# INA260_SFS.net
KiCad netlist of a schematic drawn in EAGLE
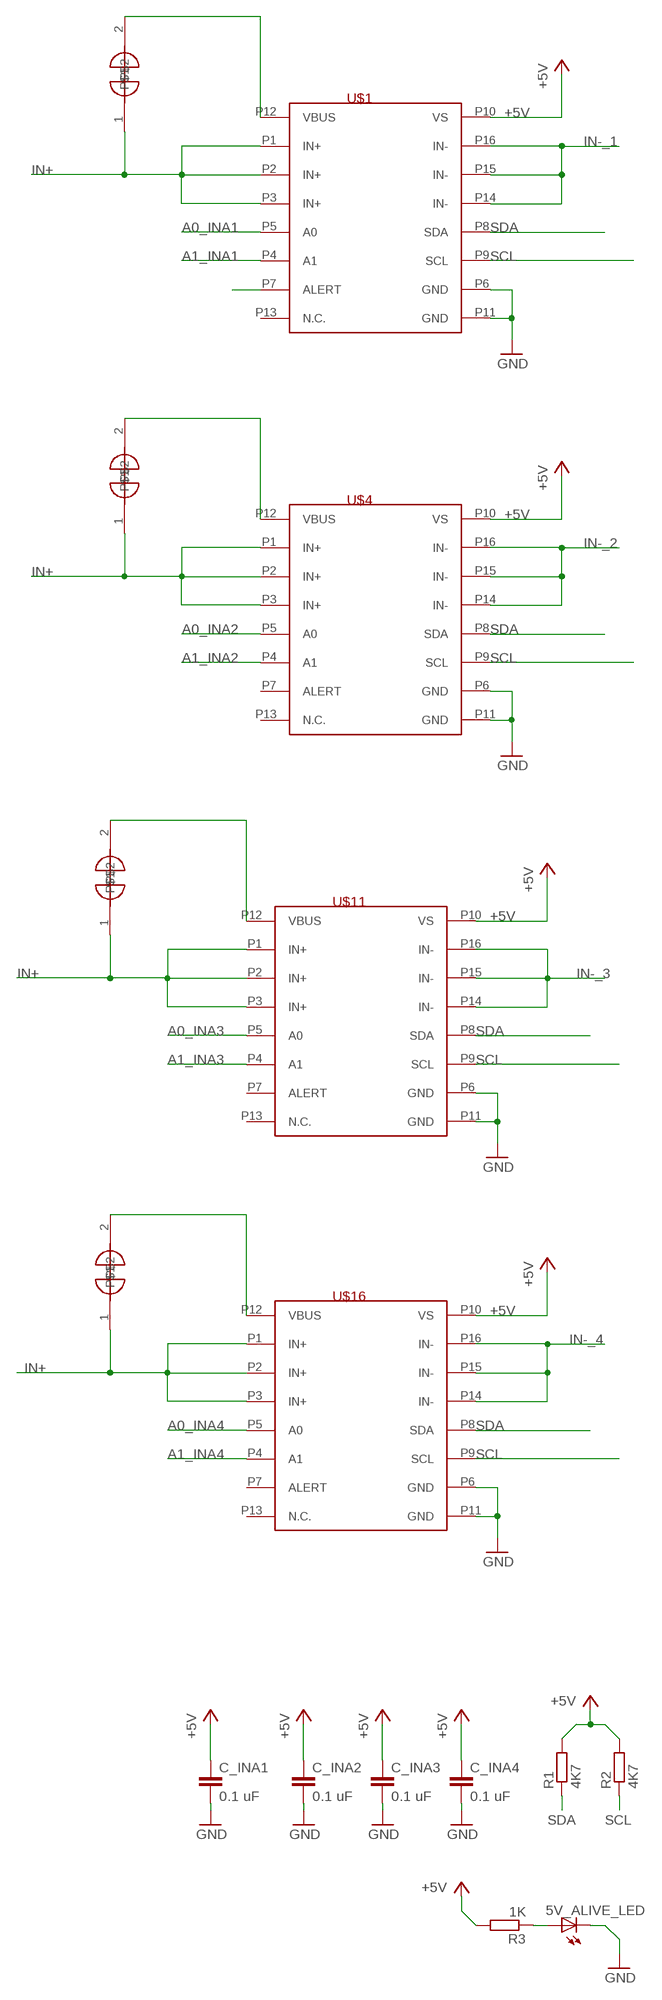
[diagram p0: schematic, sheet 1]
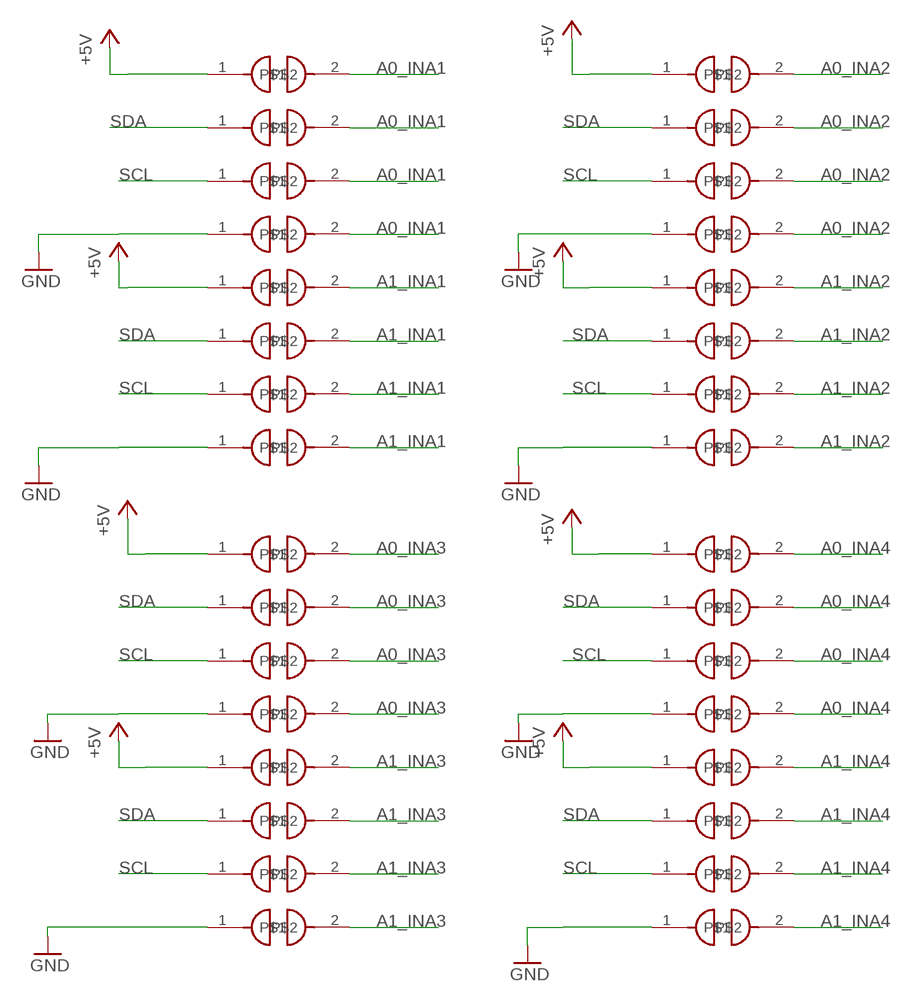
[diagram p1: schematic, sheet 2]
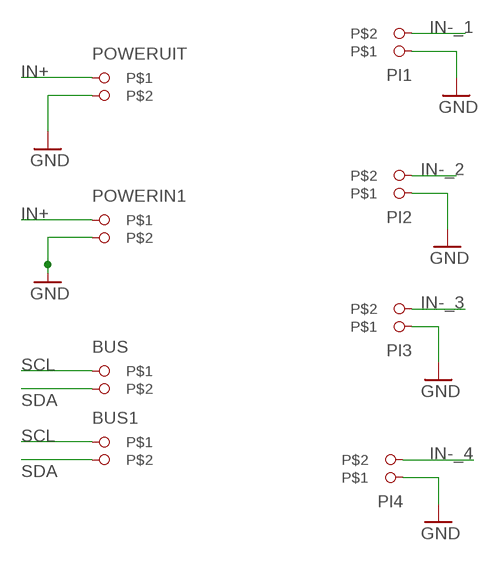
[diagram p2: schematic, sheet 3]
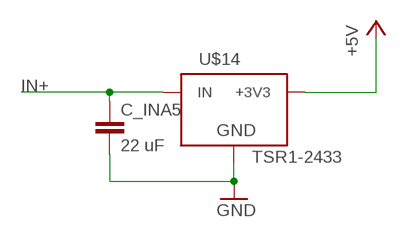
[diagram p3: schematic, sheet 4]

(export (version "E")
  (design (tool "Eeschema 10.0.6"))
  (components
    (comp (ref "BUS")
      (value "CON_3.81MM2_SIDE")
      (footprint "eagle-import:CON_3.81MM2")
      (libsource (lib "eagle-import") (part "CON_3.81MM2_SIDE"))
    )
    (comp (ref "BUS1")
      (value "CON_3.81MM2_SIDE")
      (footprint "eagle-import:CON_3.81MM2")
      (libsource (lib "eagle-import") (part "CON_3.81MM2_SIDE"))
    )
    (comp (ref "PI1")
      (value "CON_3.81MM2_SIDE")
      (footprint "eagle-import:CON_3.81MM2")
      (libsource (lib "eagle-import") (part "CON_3.81MM2_SIDE"))
    )
    (comp (ref "PI2")
      (value "CON_3.81MM2_SIDE")
      (footprint "eagle-import:CON_3.81MM2")
      (libsource (lib "eagle-import") (part "CON_3.81MM2_SIDE"))
    )
    (comp (ref "PI3")
      (value "CON_3.81MM2_SIDE")
      (footprint "eagle-import:CON_3.81MM2")
      (libsource (lib "eagle-import") (part "CON_3.81MM2_SIDE"))
    )
    (comp (ref "PI4")
      (value "CON_3.81MM2_SIDE")
      (footprint "eagle-import:CON_3.81MM2")
      (libsource (lib "eagle-import") (part "CON_3.81MM2_SIDE"))
    )
    (comp (ref "POWERIN1")
      (value "CON_3.81MM2_SIDE")
      (footprint "eagle-import:CON_3.81MM2")
      (libsource (lib "eagle-import") (part "CON_3.81MM2_SIDE"))
    )
    (comp (ref "POWERUIT")
      (value "CON_3.81MM2_SIDE")
      (footprint "eagle-import:CON_3.81MM2")
      (libsource (lib "eagle-import") (part "CON_3.81MM2_SIDE"))
    )
    (comp (ref "U$38")
      (value "JUMPER")
      (footprint "eagle-import:SOLDERJUMPER_ARROW_NOPASTE")
      (libsource (lib "eagle-import") (part "JUMPER"))
    )
    (comp (ref "U$39")
      (value "JUMPER")
      (footprint "eagle-import:SOLDERJUMPER_ARROW_NOPASTE")
      (libsource (lib "eagle-import") (part "JUMPER"))
    )
    (comp (ref "U$40")
      (value "JUMPER")
      (footprint "eagle-import:SOLDERJUMPER_ARROW_NOPASTE")
      (libsource (lib "eagle-import") (part "JUMPER"))
    )
    (comp (ref "U$41")
      (value "JUMPER")
      (footprint "eagle-import:SOLDERJUMPER_ARROW_NOPASTE")
      (libsource (lib "eagle-import") (part "JUMPER"))
    )
    (comp (ref "U$42")
      (value "JUMPER")
      (footprint "eagle-import:SOLDERJUMPER_ARROW_NOPASTE")
      (libsource (lib "eagle-import") (part "JUMPER"))
    )
    (comp (ref "U$43")
      (value "JUMPER")
      (footprint "eagle-import:SOLDERJUMPER_ARROW_NOPASTE")
      (libsource (lib "eagle-import") (part "JUMPER"))
    )
    (comp (ref "U$44")
      (value "JUMPER")
      (footprint "eagle-import:SOLDERJUMPER_ARROW_NOPASTE")
      (libsource (lib "eagle-import") (part "JUMPER"))
    )
    (comp (ref "U$45")
      (value "JUMPER")
      (footprint "eagle-import:SOLDERJUMPER_ARROW_NOPASTE")
      (libsource (lib "eagle-import") (part "JUMPER"))
    )
    (comp (ref "U$46")
      (value "JUMPER")
      (footprint "eagle-import:SOLDERJUMPER_ARROW_NOPASTE")
      (libsource (lib "eagle-import") (part "JUMPER"))
    )
    (comp (ref "U$47")
      (value "JUMPER")
      (footprint "eagle-import:SOLDERJUMPER_ARROW_NOPASTE")
      (libsource (lib "eagle-import") (part "JUMPER"))
    )
    (comp (ref "U$48")
      (value "JUMPER")
      (footprint "eagle-import:SOLDERJUMPER_ARROW_NOPASTE")
      (libsource (lib "eagle-import") (part "JUMPER"))
    )
    (comp (ref "U$49")
      (value "JUMPER")
      (footprint "eagle-import:SOLDERJUMPER_ARROW_NOPASTE")
      (libsource (lib "eagle-import") (part "JUMPER"))
    )
    (comp (ref "U$50")
      (value "JUMPER")
      (footprint "eagle-import:SOLDERJUMPER_ARROW_NOPASTE")
      (libsource (lib "eagle-import") (part "JUMPER"))
    )
    (comp (ref "U$51")
      (value "JUMPER")
      (footprint "eagle-import:SOLDERJUMPER_ARROW_NOPASTE")
      (libsource (lib "eagle-import") (part "JUMPER"))
    )
    (comp (ref "U$52")
      (value "JUMPER")
      (footprint "eagle-import:SOLDERJUMPER_ARROW_NOPASTE")
      (libsource (lib "eagle-import") (part "JUMPER"))
    )
    (comp (ref "U$53")
      (value "JUMPER")
      (footprint "eagle-import:SOLDERJUMPER_ARROW_NOPASTE")
      (libsource (lib "eagle-import") (part "JUMPER"))
    )
    (comp (ref "U$54")
      (value "JUMPER")
      (footprint "eagle-import:SOLDERJUMPER_ARROW_NOPASTE")
      (libsource (lib "eagle-import") (part "JUMPER"))
    )
    (comp (ref "U$55")
      (value "JUMPER")
      (footprint "eagle-import:SOLDERJUMPER_ARROW_NOPASTE")
      (libsource (lib "eagle-import") (part "JUMPER"))
    )
    (comp (ref "U$56")
      (value "JUMPER")
      (footprint "eagle-import:SOLDERJUMPER_ARROW_NOPASTE")
      (libsource (lib "eagle-import") (part "JUMPER"))
    )
    (comp (ref "U$57")
      (value "JUMPER")
      (footprint "eagle-import:SOLDERJUMPER_ARROW_NOPASTE")
      (libsource (lib "eagle-import") (part "JUMPER"))
    )
    (comp (ref "U$58")
      (value "JUMPER")
      (footprint "eagle-import:SOLDERJUMPER_ARROW_NOPASTE")
      (libsource (lib "eagle-import") (part "JUMPER"))
    )
    (comp (ref "U$59")
      (value "JUMPER")
      (footprint "eagle-import:SOLDERJUMPER_ARROW_NOPASTE")
      (libsource (lib "eagle-import") (part "JUMPER"))
    )
    (comp (ref "U$60")
      (value "JUMPER")
      (footprint "eagle-import:SOLDERJUMPER_ARROW_NOPASTE")
      (libsource (lib "eagle-import") (part "JUMPER"))
    )
    (comp (ref "U$61")
      (value "JUMPER")
      (footprint "eagle-import:SOLDERJUMPER_ARROW_NOPASTE")
      (libsource (lib "eagle-import") (part "JUMPER"))
    )
    (comp (ref "U$62")
      (value "JUMPER")
      (footprint "eagle-import:SOLDERJUMPER_ARROW_NOPASTE")
      (libsource (lib "eagle-import") (part "JUMPER"))
    )
    (comp (ref "U$63")
      (value "JUMPER")
      (footprint "eagle-import:SOLDERJUMPER_ARROW_NOPASTE")
      (libsource (lib "eagle-import") (part "JUMPER"))
    )
    (comp (ref "U$64")
      (value "JUMPER")
      (footprint "eagle-import:SOLDERJUMPER_ARROW_NOPASTE")
      (libsource (lib "eagle-import") (part "JUMPER"))
    )
    (comp (ref "U$65")
      (value "JUMPER")
      (footprint "eagle-import:SOLDERJUMPER_ARROW_NOPASTE")
      (libsource (lib "eagle-import") (part "JUMPER"))
    )
    (comp (ref "U$66")
      (value "JUMPER")
      (footprint "eagle-import:SOLDERJUMPER_ARROW_NOPASTE")
      (libsource (lib "eagle-import") (part "JUMPER"))
    )
    (comp (ref "U$67")
      (value "JUMPER")
      (footprint "eagle-import:SOLDERJUMPER_ARROW_NOPASTE")
      (libsource (lib "eagle-import") (part "JUMPER"))
    )
    (comp (ref "U$68")
      (value "JUMPER")
      (footprint "eagle-import:SOLDERJUMPER_ARROW_NOPASTE")
      (libsource (lib "eagle-import") (part "JUMPER"))
    )
    (comp (ref "U$69")
      (value "JUMPER")
      (footprint "eagle-import:SOLDERJUMPER_ARROW_NOPASTE")
      (libsource (lib "eagle-import") (part "JUMPER"))
    )
    (comp (ref "5V_ALIVE_LED")
      (value "LEDSMT1206")
      (footprint "eagle-import:1206")
      (libsource (lib "eagle-import") (part "LEDSMT1206"))
    )
    (comp (ref "C_INA1")
      (value "0.1 uF")
      (footprint "eagle-import:RESC0805_N")
      (libsource (lib "eagle-import") (part "CAPACITOR_0805_N"))
    )
    (comp (ref "C_INA2")
      (value "0.1 uF")
      (footprint "eagle-import:RESC0805_N")
      (libsource (lib "eagle-import") (part "CAPACITOR_0805_N"))
    )
    (comp (ref "C_INA3")
      (value "0.1 uF")
      (footprint "eagle-import:RESC0805_N")
      (libsource (lib "eagle-import") (part "CAPACITOR_0805_N"))
    )
    (comp (ref "C_INA4")
      (value "0.1 uF")
      (footprint "eagle-import:RESC0805_N")
      (libsource (lib "eagle-import") (part "CAPACITOR_0805_N"))
    )
    (comp (ref "R1")
      (value "4K7")
      (footprint "eagle-import:M0805")
      (libsource (lib "eagle-import") (part "R-EU_M0805"))
    )
    (comp (ref "R2")
      (value "4K7")
      (footprint "eagle-import:M0805")
      (libsource (lib "eagle-import") (part "R-EU_M0805"))
    )
    (comp (ref "R3")
      (value "1K")
      (footprint "eagle-import:M0805")
      (libsource (lib "eagle-import") (part "R-EU_M0805"))
    )
    (comp (ref "U$1")
      (value "INA260")
      (footprint "eagle-import:TSSOP16L")
      (libsource (lib "eagle-import") (part "INA260"))
    )
    (comp (ref "U$4")
      (value "INA260")
      (footprint "eagle-import:TSSOP16L")
      (libsource (lib "eagle-import") (part "INA260"))
    )
    (comp (ref "U$5")
      (value "CLOSEDJUMPER")
      (footprint "eagle-import:SOLDERJUMPER_CLOSEDWIRE")
      (libsource (lib "eagle-import") (part "CLOSEDJUMPER"))
    )
    (comp (ref "U$6")
      (value "CLOSEDJUMPER")
      (footprint "eagle-import:SOLDERJUMPER_CLOSEDWIRE")
      (libsource (lib "eagle-import") (part "CLOSEDJUMPER"))
    )
    (comp (ref "U$11")
      (value "INA260")
      (footprint "eagle-import:TSSOP16L")
      (libsource (lib "eagle-import") (part "INA260"))
    )
    (comp (ref "U$12")
      (value "CLOSEDJUMPER")
      (footprint "eagle-import:SOLDERJUMPER_CLOSEDWIRE")
      (libsource (lib "eagle-import") (part "CLOSEDJUMPER"))
    )
    (comp (ref "U$16")
      (value "INA260")
      (footprint "eagle-import:TSSOP16L")
      (libsource (lib "eagle-import") (part "INA260"))
    )
    (comp (ref "U$17")
      (value "CLOSEDJUMPER")
      (footprint "eagle-import:SOLDERJUMPER_CLOSEDWIRE")
      (libsource (lib "eagle-import") (part "CLOSEDJUMPER"))
    )
    (comp (ref "C_INA5")
      (value "22 uF")
      (footprint "eagle-import:RESC0805_N")
      (libsource (lib "eagle-import") (part "CAPACITOR_0805_N"))
    )
    (comp (ref "U$14")
      (value "TSR1-2433")
      (footprint "eagle-import:TSR-1")
      (libsource (lib "eagle-import") (part "TSR1-2433"))
    )
  )
  (nets
    (net (code "1") (name "+5V") (class "Default")
      (node (ref "C_INA1") (pin "1") (pinfunction "1_1") (pintype "passive"))
      (node (ref "C_INA2") (pin "1") (pinfunction "1_1") (pintype "passive"))
      (node (ref "C_INA3") (pin "1") (pinfunction "1_1") (pintype "passive"))
      (node (ref "C_INA4") (pin "1") (pinfunction "1_1") (pintype "passive"))
      (node (ref "R1") (pin "2") (pinfunction "2_2") (pintype "passive"))
      (node (ref "R2") (pin "2") (pinfunction "2_2") (pintype "passive"))
      (node (ref "R3") (pin "2") (pinfunction "2_2") (pintype "passive"))
      (node (ref "U$1") (pin "P10") (pinfunction "VS_P10") (pintype "bidirectional"))
      (node (ref "U$11") (pin "P10") (pinfunction "VS_P10") (pintype "bidirectional"))
      (node (ref "U$14") (pin "3") (pinfunction "+3V3_3") (pintype "power_in"))
      (node (ref "U$16") (pin "P10") (pinfunction "VS_P10") (pintype "bidirectional"))
      (node (ref "U$4") (pin "P10") (pinfunction "VS_P10") (pintype "bidirectional"))
      (node (ref "U$41") (pin "1") (pinfunction "P$1_1") (pintype "bidirectional"))
      (node (ref "U$45") (pin "1") (pinfunction "P$1_1") (pintype "bidirectional"))
      (node (ref "U$49") (pin "1") (pinfunction "P$1_1") (pintype "bidirectional"))
      (node (ref "U$53") (pin "1") (pinfunction "P$1_1") (pintype "bidirectional"))
      (node (ref "U$57") (pin "1") (pinfunction "P$1_1") (pintype "bidirectional"))
      (node (ref "U$61") (pin "1") (pinfunction "P$1_1") (pintype "bidirectional"))
      (node (ref "U$65") (pin "1") (pinfunction "P$1_1") (pintype "bidirectional"))
      (node (ref "U$69") (pin "1") (pinfunction "P$1_1") (pintype "bidirectional"))
    )
    (net (code "2") (name "A0_INA1") (class "Default")
      (node (ref "U$1") (pin "P5") (pinfunction "A0_P5") (pintype "bidirectional"))
      (node (ref "U$42") (pin "2") (pinfunction "P$2_2") (pintype "bidirectional"))
      (node (ref "U$43") (pin "2") (pinfunction "P$2_2") (pintype "bidirectional"))
      (node (ref "U$44") (pin "2") (pinfunction "P$2_2") (pintype "bidirectional"))
      (node (ref "U$45") (pin "2") (pinfunction "P$2_2") (pintype "bidirectional"))
    )
    (net (code "3") (name "A0_INA2") (class "Default")
      (node (ref "U$4") (pin "P5") (pinfunction "A0_P5") (pintype "bidirectional"))
      (node (ref "U$50") (pin "2") (pinfunction "P$2_2") (pintype "bidirectional"))
      (node (ref "U$51") (pin "2") (pinfunction "P$2_2") (pintype "bidirectional"))
      (node (ref "U$52") (pin "2") (pinfunction "P$2_2") (pintype "bidirectional"))
      (node (ref "U$53") (pin "2") (pinfunction "P$2_2") (pintype "bidirectional"))
    )
    (net (code "4") (name "A0_INA3") (class "Default")
      (node (ref "U$11") (pin "P5") (pinfunction "A0_P5") (pintype "bidirectional"))
      (node (ref "U$58") (pin "2") (pinfunction "P$2_2") (pintype "bidirectional"))
      (node (ref "U$59") (pin "2") (pinfunction "P$2_2") (pintype "bidirectional"))
      (node (ref "U$60") (pin "2") (pinfunction "P$2_2") (pintype "bidirectional"))
      (node (ref "U$61") (pin "2") (pinfunction "P$2_2") (pintype "bidirectional"))
    )
    (net (code "5") (name "A0_INA4") (class "Default")
      (node (ref "U$16") (pin "P5") (pinfunction "A0_P5") (pintype "bidirectional"))
      (node (ref "U$66") (pin "2") (pinfunction "P$2_2") (pintype "bidirectional"))
      (node (ref "U$67") (pin "2") (pinfunction "P$2_2") (pintype "bidirectional"))
      (node (ref "U$68") (pin "2") (pinfunction "P$2_2") (pintype "bidirectional"))
      (node (ref "U$69") (pin "2") (pinfunction "P$2_2") (pintype "bidirectional"))
    )
    (net (code "6") (name "A1_INA1") (class "Default")
      (node (ref "U$1") (pin "P4") (pinfunction "A1_P4") (pintype "bidirectional"))
      (node (ref "U$38") (pin "2") (pinfunction "P$2_2") (pintype "bidirectional"))
      (node (ref "U$39") (pin "2") (pinfunction "P$2_2") (pintype "bidirectional"))
      (node (ref "U$40") (pin "2") (pinfunction "P$2_2") (pintype "bidirectional"))
      (node (ref "U$41") (pin "2") (pinfunction "P$2_2") (pintype "bidirectional"))
    )
    (net (code "7") (name "A1_INA2") (class "Default")
      (node (ref "U$4") (pin "P4") (pinfunction "A1_P4") (pintype "bidirectional"))
      (node (ref "U$46") (pin "2") (pinfunction "P$2_2") (pintype "bidirectional"))
      (node (ref "U$47") (pin "2") (pinfunction "P$2_2") (pintype "bidirectional"))
      (node (ref "U$48") (pin "2") (pinfunction "P$2_2") (pintype "bidirectional"))
      (node (ref "U$49") (pin "2") (pinfunction "P$2_2") (pintype "bidirectional"))
    )
    (net (code "8") (name "A1_INA3") (class "Default")
      (node (ref "U$11") (pin "P4") (pinfunction "A1_P4") (pintype "bidirectional"))
      (node (ref "U$54") (pin "2") (pinfunction "P$2_2") (pintype "bidirectional"))
      (node (ref "U$55") (pin "2") (pinfunction "P$2_2") (pintype "bidirectional"))
      (node (ref "U$56") (pin "2") (pinfunction "P$2_2") (pintype "bidirectional"))
      (node (ref "U$57") (pin "2") (pinfunction "P$2_2") (pintype "bidirectional"))
    )
    (net (code "9") (name "A1_INA4") (class "Default")
      (node (ref "U$16") (pin "P4") (pinfunction "A1_P4") (pintype "bidirectional"))
      (node (ref "U$62") (pin "2") (pinfunction "P$2_2") (pintype "bidirectional"))
      (node (ref "U$63") (pin "2") (pinfunction "P$2_2") (pintype "bidirectional"))
      (node (ref "U$64") (pin "2") (pinfunction "P$2_2") (pintype "bidirectional"))
      (node (ref "U$65") (pin "2") (pinfunction "P$2_2") (pintype "bidirectional"))
    )
    (net (code "10") (name "GND") (class "Default")
      (node (ref "5V_ALIVE_LED") (pin "C") (pinfunction "C_C") (pintype "passive"))
      (node (ref "C_INA1") (pin "2") (pinfunction "2_2") (pintype "passive"))
      (node (ref "C_INA2") (pin "2") (pinfunction "2_2") (pintype "passive"))
      (node (ref "C_INA3") (pin "2") (pinfunction "2_2") (pintype "passive"))
      (node (ref "C_INA4") (pin "2") (pinfunction "2_2") (pintype "passive"))
      (node (ref "C_INA5") (pin "2") (pinfunction "2_2") (pintype "passive"))
      (node (ref "PI1") (pin "P$1") (pinfunction "P$1_P$1") (pintype "bidirectional"))
      (node (ref "PI2") (pin "P$1") (pinfunction "P$1_P$1") (pintype "bidirectional"))
      (node (ref "PI3") (pin "P$1") (pinfunction "P$1_P$1") (pintype "bidirectional"))
      (node (ref "PI4") (pin "P$1") (pinfunction "P$1_P$1") (pintype "bidirectional"))
      (node (ref "POWERIN1") (pin "P$2") (pinfunction "P$2_P$2") (pintype "bidirectional"))
      (node (ref "POWERUIT") (pin "P$2") (pinfunction "P$2_P$2") (pintype "bidirectional"))
      (node (ref "U$1") (pin "P11") (pinfunction "GND_P11") (pintype "bidirectional"))
      (node (ref "U$1") (pin "P6") (pinfunction "GND_P6") (pintype "bidirectional"))
      (node (ref "U$11") (pin "P11") (pinfunction "GND_P11") (pintype "bidirectional"))
      (node (ref "U$11") (pin "P6") (pinfunction "GND_P6") (pintype "bidirectional"))
      (node (ref "U$14") (pin "2") (pinfunction "GND_2") (pintype "power_in"))
      (node (ref "U$16") (pin "P11") (pinfunction "GND_P11") (pintype "bidirectional"))
      (node (ref "U$16") (pin "P6") (pinfunction "GND_P6") (pintype "bidirectional"))
      (node (ref "U$38") (pin "1") (pinfunction "P$1_1") (pintype "bidirectional"))
      (node (ref "U$4") (pin "P11") (pinfunction "GND_P11") (pintype "bidirectional"))
      (node (ref "U$4") (pin "P6") (pinfunction "GND_P6") (pintype "bidirectional"))
      (node (ref "U$42") (pin "1") (pinfunction "P$1_1") (pintype "bidirectional"))
      (node (ref "U$46") (pin "1") (pinfunction "P$1_1") (pintype "bidirectional"))
      (node (ref "U$50") (pin "1") (pinfunction "P$1_1") (pintype "bidirectional"))
      (node (ref "U$54") (pin "1") (pinfunction "P$1_1") (pintype "bidirectional"))
      (node (ref "U$58") (pin "1") (pinfunction "P$1_1") (pintype "bidirectional"))
      (node (ref "U$62") (pin "1") (pinfunction "P$1_1") (pintype "bidirectional"))
      (node (ref "U$66") (pin "1") (pinfunction "P$1_1") (pintype "bidirectional"))
    )
    (net (code "11") (name "IN+") (class "Default")
      (node (ref "C_INA5") (pin "1") (pinfunction "1_1") (pintype "passive"))
      (node (ref "POWERIN1") (pin "P$1") (pinfunction "P$1_P$1") (pintype "bidirectional"))
      (node (ref "POWERUIT") (pin "P$1") (pinfunction "P$1_P$1") (pintype "bidirectional"))
      (node (ref "U$1") (pin "P1") (pinfunction "IN+_P1") (pintype "bidirectional"))
      (node (ref "U$1") (pin "P2") (pinfunction "IN+_P2") (pintype "bidirectional"))
      (node (ref "U$1") (pin "P3") (pinfunction "IN+_P3") (pintype "bidirectional"))
      (node (ref "U$11") (pin "P1") (pinfunction "IN+_P1") (pintype "bidirectional"))
      (node (ref "U$11") (pin "P2") (pinfunction "IN+_P2") (pintype "bidirectional"))
      (node (ref "U$11") (pin "P3") (pinfunction "IN+_P3") (pintype "bidirectional"))
      (node (ref "U$12") (pin "1") (pinfunction "P$1_1") (pintype "bidirectional"))
      (node (ref "U$14") (pin "1") (pinfunction "IN_1") (pintype "power_in"))
      (node (ref "U$16") (pin "P1") (pinfunction "IN+_P1") (pintype "bidirectional"))
      (node (ref "U$16") (pin "P2") (pinfunction "IN+_P2") (pintype "bidirectional"))
      (node (ref "U$16") (pin "P3") (pinfunction "IN+_P3") (pintype "bidirectional"))
      (node (ref "U$17") (pin "1") (pinfunction "P$1_1") (pintype "bidirectional"))
      (node (ref "U$4") (pin "P1") (pinfunction "IN+_P1") (pintype "bidirectional"))
      (node (ref "U$4") (pin "P2") (pinfunction "IN+_P2") (pintype "bidirectional"))
      (node (ref "U$4") (pin "P3") (pinfunction "IN+_P3") (pintype "bidirectional"))
      (node (ref "U$5") (pin "1") (pinfunction "P$1_1") (pintype "bidirectional"))
      (node (ref "U$6") (pin "1") (pinfunction "P$1_1") (pintype "bidirectional"))
    )
    (net (code "12") (name "IN-_1") (class "Default")
      (node (ref "PI1") (pin "P$2") (pinfunction "P$2_P$2") (pintype "bidirectional"))
      (node (ref "U$1") (pin "P14") (pinfunction "IN-_P14") (pintype "bidirectional"))
      (node (ref "U$1") (pin "P15") (pinfunction "IN-_P15") (pintype "bidirectional"))
      (node (ref "U$1") (pin "P16") (pinfunction "IN-_P16") (pintype "bidirectional"))
    )
    (net (code "13") (name "IN-_2") (class "Default")
      (node (ref "PI2") (pin "P$2") (pinfunction "P$2_P$2") (pintype "bidirectional"))
      (node (ref "U$4") (pin "P14") (pinfunction "IN-_P14") (pintype "bidirectional"))
      (node (ref "U$4") (pin "P15") (pinfunction "IN-_P15") (pintype "bidirectional"))
      (node (ref "U$4") (pin "P16") (pinfunction "IN-_P16") (pintype "bidirectional"))
    )
    (net (code "14") (name "IN-_3") (class "Default")
      (node (ref "PI3") (pin "P$2") (pinfunction "P$2_P$2") (pintype "bidirectional"))
      (node (ref "U$11") (pin "P14") (pinfunction "IN-_P14") (pintype "bidirectional"))
      (node (ref "U$11") (pin "P15") (pinfunction "IN-_P15") (pintype "bidirectional"))
      (node (ref "U$11") (pin "P16") (pinfunction "IN-_P16") (pintype "bidirectional"))
    )
    (net (code "15") (name "IN-_4") (class "Default")
      (node (ref "PI4") (pin "P$2") (pinfunction "P$2_P$2") (pintype "bidirectional"))
      (node (ref "U$16") (pin "P14") (pinfunction "IN-_P14") (pintype "bidirectional"))
      (node (ref "U$16") (pin "P15") (pinfunction "IN-_P15") (pintype "bidirectional"))
      (node (ref "U$16") (pin "P16") (pinfunction "IN-_P16") (pintype "bidirectional"))
    )
    (net (code "16") (name "Net-(5V_ALIVE_LED-PadA)") (class "Default")
      (node (ref "5V_ALIVE_LED") (pin "A") (pinfunction "A_A") (pintype "passive"))
      (node (ref "R3") (pin "1") (pinfunction "1_1") (pintype "passive"))
    )
    (net (code "17") (name "Net-(U$1-VBUS)") (class "Default")
      (node (ref "U$1") (pin "P12") (pinfunction "VBUS_P12") (pintype "bidirectional"))
      (node (ref "U$6") (pin "2") (pinfunction "P$2_2") (pintype "bidirectional"))
    )
    (net (code "18") (name "Net-(U$4-VBUS)") (class "Default")
      (node (ref "U$4") (pin "P12") (pinfunction "VBUS_P12") (pintype "bidirectional"))
      (node (ref "U$5") (pin "2") (pinfunction "P$2_2") (pintype "bidirectional"))
    )
    (net (code "19") (name "Net-(U$11-VBUS)") (class "Default")
      (node (ref "U$11") (pin "P12") (pinfunction "VBUS_P12") (pintype "bidirectional"))
      (node (ref "U$12") (pin "2") (pinfunction "P$2_2") (pintype "bidirectional"))
    )
    (net (code "20") (name "Net-(U$16-VBUS)") (class "Default")
      (node (ref "U$16") (pin "P12") (pinfunction "VBUS_P12") (pintype "bidirectional"))
      (node (ref "U$17") (pin "2") (pinfunction "P$2_2") (pintype "bidirectional"))
    )
    (net (code "21") (name "SCL") (class "Default")
      (node (ref "BUS") (pin "P$1") (pinfunction "P$1_P$1") (pintype "bidirectional"))
      (node (ref "BUS1") (pin "P$1") (pinfunction "P$1_P$1") (pintype "bidirectional"))
      (node (ref "R2") (pin "1") (pinfunction "1_1") (pintype "passive"))
      (node (ref "U$1") (pin "P9") (pinfunction "SCL_P9") (pintype "bidirectional"))
      (node (ref "U$11") (pin "P9") (pinfunction "SCL_P9") (pintype "bidirectional"))
      (node (ref "U$16") (pin "P9") (pinfunction "SCL_P9") (pintype "bidirectional"))
      (node (ref "U$39") (pin "1") (pinfunction "P$1_1") (pintype "bidirectional"))
      (node (ref "U$4") (pin "P9") (pinfunction "SCL_P9") (pintype "bidirectional"))
      (node (ref "U$43") (pin "1") (pinfunction "P$1_1") (pintype "bidirectional"))
      (node (ref "U$47") (pin "1") (pinfunction "P$1_1") (pintype "bidirectional"))
      (node (ref "U$51") (pin "1") (pinfunction "P$1_1") (pintype "bidirectional"))
      (node (ref "U$55") (pin "1") (pinfunction "P$1_1") (pintype "bidirectional"))
      (node (ref "U$59") (pin "1") (pinfunction "P$1_1") (pintype "bidirectional"))
      (node (ref "U$63") (pin "1") (pinfunction "P$1_1") (pintype "bidirectional"))
      (node (ref "U$67") (pin "1") (pinfunction "P$1_1") (pintype "bidirectional"))
    )
    (net (code "22") (name "SDA") (class "Default")
      (node (ref "BUS") (pin "P$2") (pinfunction "P$2_P$2") (pintype "bidirectional"))
      (node (ref "BUS1") (pin "P$2") (pinfunction "P$2_P$2") (pintype "bidirectional"))
      (node (ref "R1") (pin "1") (pinfunction "1_1") (pintype "passive"))
      (node (ref "U$1") (pin "P8") (pinfunction "SDA_P8") (pintype "bidirectional"))
      (node (ref "U$11") (pin "P8") (pinfunction "SDA_P8") (pintype "bidirectional"))
      (node (ref "U$16") (pin "P8") (pinfunction "SDA_P8") (pintype "bidirectional"))
      (node (ref "U$4") (pin "P8") (pinfunction "SDA_P8") (pintype "bidirectional"))
      (node (ref "U$40") (pin "1") (pinfunction "P$1_1") (pintype "bidirectional"))
      (node (ref "U$44") (pin "1") (pinfunction "P$1_1") (pintype "bidirectional"))
      (node (ref "U$48") (pin "1") (pinfunction "P$1_1") (pintype "bidirectional"))
      (node (ref "U$52") (pin "1") (pinfunction "P$1_1") (pintype "bidirectional"))
      (node (ref "U$56") (pin "1") (pinfunction "P$1_1") (pintype "bidirectional"))
      (node (ref "U$60") (pin "1") (pinfunction "P$1_1") (pintype "bidirectional"))
      (node (ref "U$64") (pin "1") (pinfunction "P$1_1") (pintype "bidirectional"))
      (node (ref "U$68") (pin "1") (pinfunction "P$1_1") (pintype "bidirectional"))
    )
    (net (code "23") (name "unconnected-(U$1-ALERT-PadP7)") (class "Default")
      (node (ref "U$1") (pin "P7") (pinfunction "ALERT_P7") (pintype "bidirectional"))
    )
    (net (code "24") (name "unconnected-(U$1-N.C.-PadP13)") (class "Default")
      (node (ref "U$1") (pin "P13") (pinfunction "N.C._P13") (pintype "bidirectional"))
    )
    (net (code "25") (name "unconnected-(U$4-ALERT-PadP7)") (class "Default")
      (node (ref "U$4") (pin "P7") (pinfunction "ALERT_P7") (pintype "bidirectional"))
    )
    (net (code "26") (name "unconnected-(U$4-N.C.-PadP13)") (class "Default")
      (node (ref "U$4") (pin "P13") (pinfunction "N.C._P13") (pintype "bidirectional"))
    )
    (net (code "27") (name "unconnected-(U$11-ALERT-PadP7)") (class "Default")
      (node (ref "U$11") (pin "P7") (pinfunction "ALERT_P7") (pintype "bidirectional"))
    )
    (net (code "28") (name "unconnected-(U$11-N.C.-PadP13)") (class "Default")
      (node (ref "U$11") (pin "P13") (pinfunction "N.C._P13") (pintype "bidirectional"))
    )
    (net (code "29") (name "unconnected-(U$16-ALERT-PadP7)") (class "Default")
      (node (ref "U$16") (pin "P7") (pinfunction "ALERT_P7") (pintype "bidirectional"))
    )
    (net (code "30") (name "unconnected-(U$16-N.C.-PadP13)") (class "Default")
      (node (ref "U$16") (pin "P13") (pinfunction "N.C._P13") (pintype "bidirectional"))
    )
  )
)
